# Uno_Shield.net
KiCad netlist of a schematic drawn in EAGLE
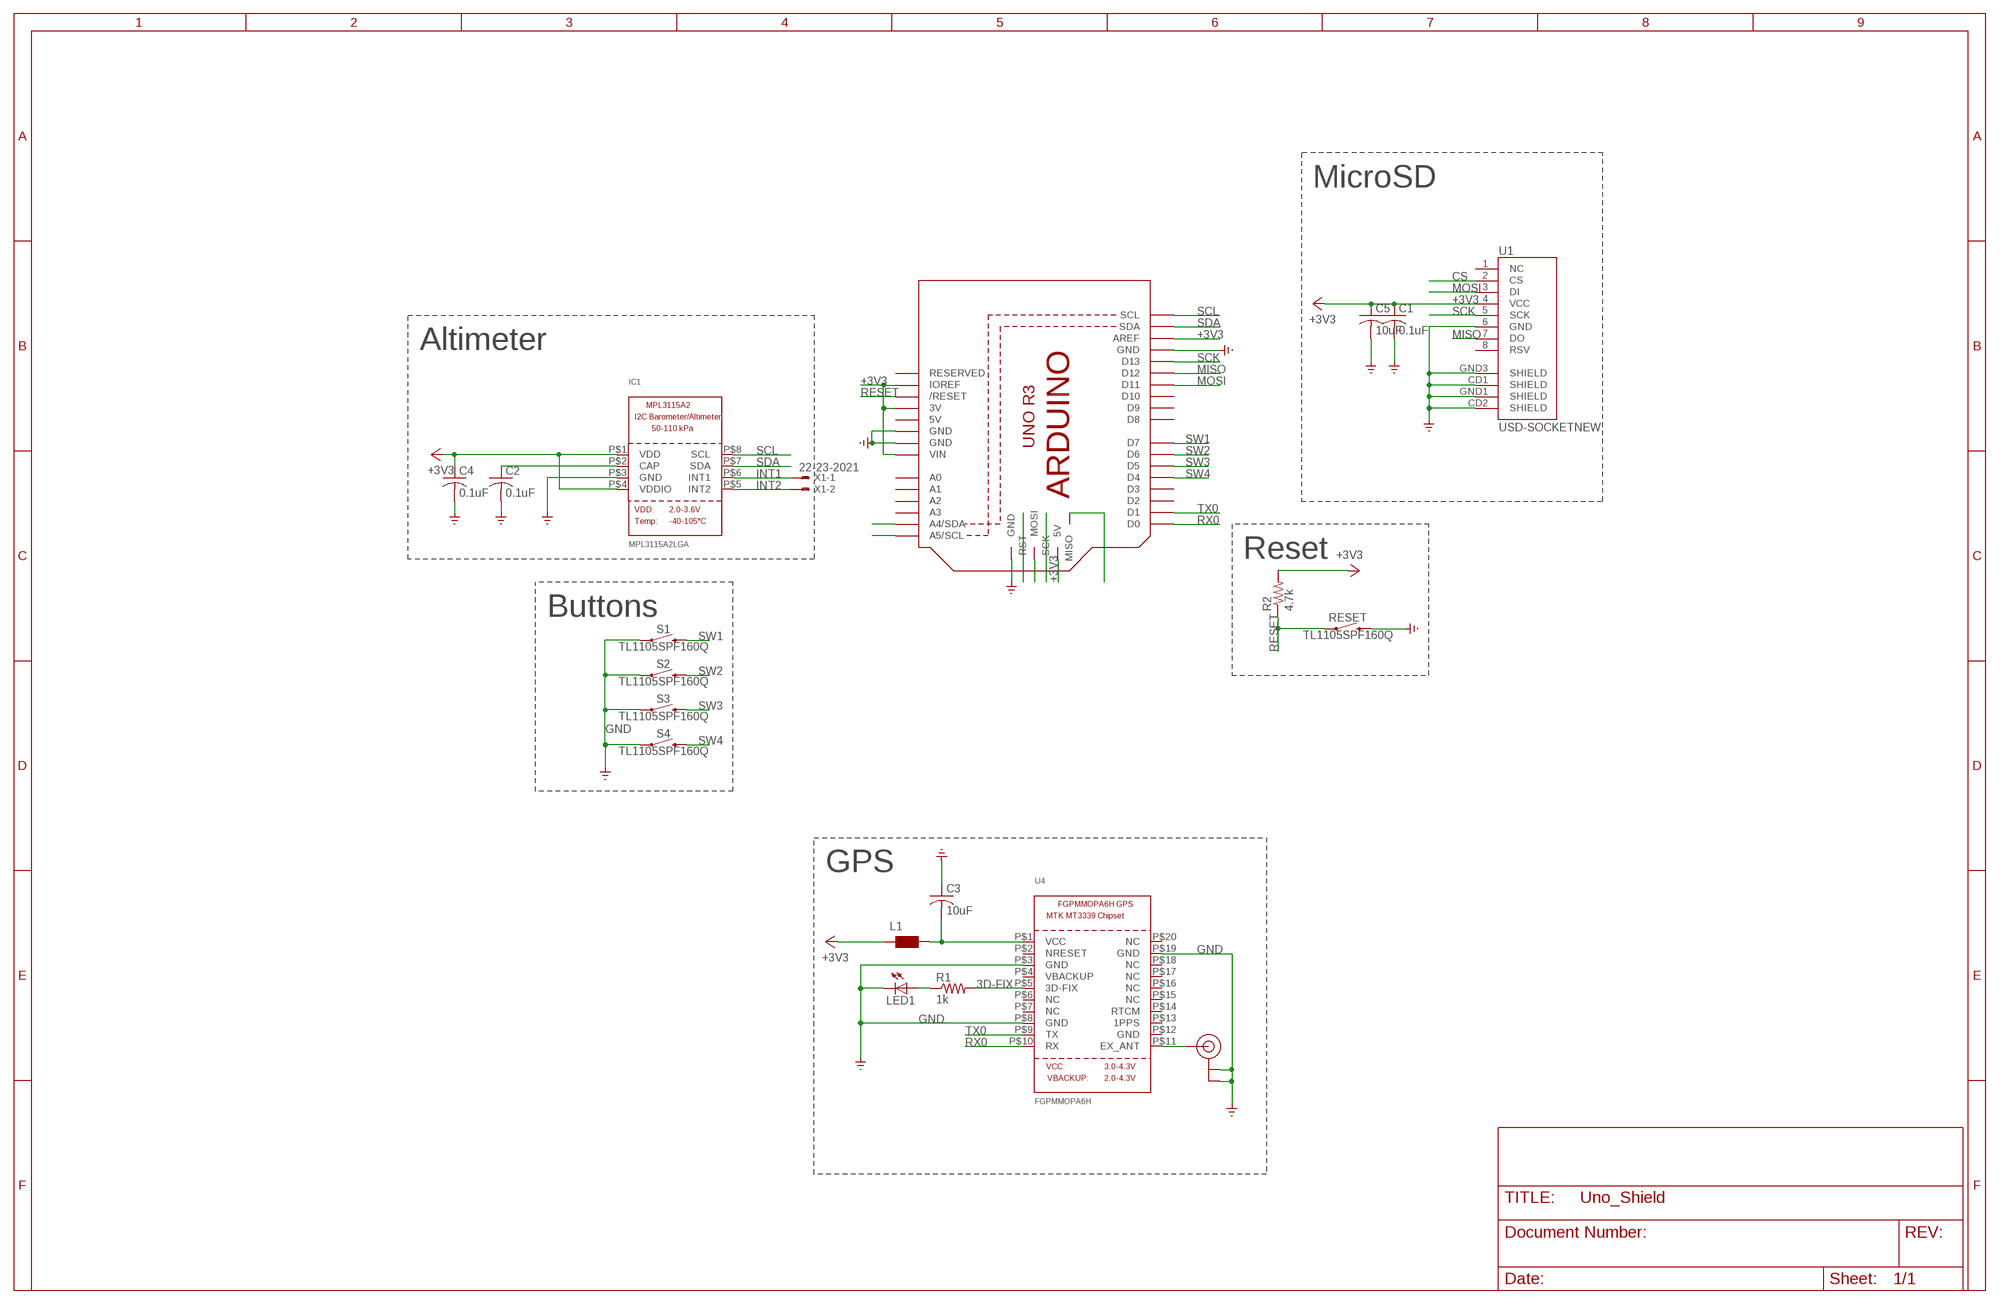
[diagram p0: schematic, sheet 1]

(export (version "E")
  (design (tool "Eeschema 10.0.6"))
  (components
    (comp (ref "C1")
      (value "0.1uF")
      (footprint "eagle-import:C1206")
      (libsource (lib "eagle-import") (part "C-USC1206"))
    )
    (comp (ref "C2")
      (value "0.1uF")
      (footprint "eagle-import:C1206")
      (libsource (lib "eagle-import") (part "C-USC1206"))
    )
    (comp (ref "C3")
      (value "10uF")
      (footprint "eagle-import:C1206")
      (libsource (lib "eagle-import") (part "C-USC1206"))
    )
    (comp (ref "C4")
      (value "0.1uF")
      (footprint "eagle-import:C1206")
      (libsource (lib "eagle-import") (part "C-USC1206"))
    )
    (comp (ref "C5")
      (value "10uF")
      (footprint "eagle-import:C1206")
      (libsource (lib "eagle-import") (part "C-USC1206"))
    )
    (comp (ref "IC1")
      (value "MPL3115A2LGA")
      (footprint "eagle-import:LGA8")
      (libsource (lib "eagle-import") (part "MPL3115A2LGA"))
    )
    (comp (ref "L1")
      (value "WE-CBF_1206")
      (footprint "eagle-import:1206")
      (libsource (lib "eagle-import") (part "WE-CBF_1206"))
    )
    (comp (ref "LED1")
      (value "LEDSMT1206")
      (footprint "eagle-import:1206")
      (libsource (lib "eagle-import") (part "LEDSMT1206"))
    )
    (comp (ref "M1")
      (value "ARDUINO_R3_ICSP")
      (footprint "eagle-import:ARDUINOR3_ICSP")
      (libsource (lib "eagle-import") (part "ARDUINO_R3_ICSP"))
    )
    (comp (ref "R1")
      (value "1k")
      (footprint "eagle-import:R1206")
      (libsource (lib "eagle-import") (part "R-US_R1206"))
    )
    (comp (ref "R2")
      (value "4.7k")
      (footprint "eagle-import:R1206")
      (libsource (lib "eagle-import") (part "R-US_R1206"))
    )
    (comp (ref "RESET")
      (value "TL1105SPF160Q")
      (footprint "eagle-import:TACTILE_SWITCH_PTH_6.0MM")
      (libsource (lib "eagle-import") (part "MOMENTARY-SWITCH-SPST-PTH-6.0MM"))
    )
    (comp (ref "S1")
      (value "TL1105SPF160Q")
      (footprint "eagle-import:TACTILE_SWITCH_PTH_6.0MM")
      (libsource (lib "eagle-import") (part "MOMENTARY-SWITCH-SPST-PTH-6.0MM"))
    )
    (comp (ref "S2")
      (value "TL1105SPF160Q")
      (footprint "eagle-import:TACTILE_SWITCH_PTH_6.0MM")
      (libsource (lib "eagle-import") (part "MOMENTARY-SWITCH-SPST-PTH-6.0MM"))
    )
    (comp (ref "S3")
      (value "TL1105SPF160Q")
      (footprint "eagle-import:TACTILE_SWITCH_PTH_6.0MM")
      (libsource (lib "eagle-import") (part "MOMENTARY-SWITCH-SPST-PTH-6.0MM"))
    )
    (comp (ref "S4")
      (value "TL1105SPF160Q")
      (footprint "eagle-import:TACTILE_SWITCH_PTH_6.0MM")
      (libsource (lib "eagle-import") (part "MOMENTARY-SWITCH-SPST-PTH-6.0MM"))
    )
    (comp (ref "U$20")
      (value "U.FL")
      (footprint "eagle-import:U.FL")
      (libsource (lib "eagle-import") (part "U.FL"))
    )
    (comp (ref "U1")
      (value "USD-SOCKETNEW")
      (footprint "eagle-import:MICRO-SD-SOCKET-PP")
      (libsource (lib "eagle-import") (part "USD-SOCKETNEW"))
    )
    (comp (ref "U4")
      (value "FGPMMOPA6H")
      (footprint "eagle-import:FGPMMOPA6H")
      (libsource (lib "eagle-import") (part "GPS_FGPMMOPA6H"))
    )
    (comp (ref "X1")
      (value "22-23-2021")
      (footprint "eagle-import:22-23-2021")
      (fields (field (name "MF") "MOLEX"))
      (libsource (lib "eagle-import") (part "22-23-2021"))
    )
  )
  (nets
    (net (code "1") (name "+3V3") (class "Default")
      (node (ref "C1") (pin "1") (pinfunction "1_1") (pintype "passive"))
      (node (ref "C4") (pin "1") (pinfunction "1_1") (pintype "passive"))
      (node (ref "C5") (pin "1") (pinfunction "1_1") (pintype "passive"))
      (node (ref "IC1") (pin "P$1") (pinfunction "VDD_P$1") (pintype "power_in"))
      (node (ref "IC1") (pin "P$4") (pinfunction "VDDIO_P$4") (pintype "power_in"))
      (node (ref "L1") (pin "1") (pinfunction "1_1") (pintype "passive"))
      (node (ref "M1") (pin "3V") (pinfunction "3V_3V") (pintype "power_in"))
      (node (ref "M1") (pin "5V_ICSP") (pinfunction "5V_5V_ICSP") (pintype "passive"))
      (node (ref "M1") (pin "AREF") (pinfunction "AREF_AREF") (pintype "bidirectional"))
      (node (ref "M1") (pin "IOREF") (pinfunction "IOREF_IOREF") (pintype "output"))
      (node (ref "M1") (pin "VIN") (pinfunction "VIN_VIN") (pintype "power_in"))
      (node (ref "R2") (pin "2") (pinfunction "2_2") (pintype "passive"))
      (node (ref "U1") (pin "4") (pinfunction "VCC_4") (pintype "bidirectional"))
    )
    (net (code "2") (name "/3D-FIX") (class "Default")
      (node (ref "R1") (pin "2") (pinfunction "2_2") (pintype "passive"))
      (node (ref "U4") (pin "P$5") (pinfunction "3D-FIX_P$5") (pintype "bidirectional"))
    )
    (net (code "3") (name "/5V") (class "Default")
      (node (ref "M1") (pin "5V") (pinfunction "5V_5V") (pintype "power_in"))
    )
    (net (code "4") (name "/CS") (class "Default")
      (node (ref "U1") (pin "2") (pinfunction "CS_2") (pintype "bidirectional"))
    )
    (net (code "5") (name "/INT1") (class "Default")
      (node (ref "IC1") (pin "P$6") (pinfunction "INT1_P$6") (pintype "output"))
      (node (ref "X1") (pin "1") (pinfunction "S_1") (pintype "passive"))
    )
    (net (code "6") (name "/INT2") (class "Default")
      (node (ref "IC1") (pin "P$5") (pinfunction "INT2_P$5") (pintype "output"))
      (node (ref "X1") (pin "2") (pinfunction "S_2") (pintype "passive"))
    )
    (net (code "7") (name "/MISO") (class "Default")
      (node (ref "M1") (pin "D12") (pinfunction "D12_D12") (pintype "bidirectional"))
      (node (ref "M1") (pin "MISO") (pinfunction "MISO_MISO") (pintype "passive"))
      (node (ref "U1") (pin "7") (pinfunction "DO_7") (pintype "bidirectional"))
    )
    (net (code "8") (name "/MOSI") (class "Default")
      (node (ref "M1") (pin "D11") (pinfunction "D11_D11") (pintype "bidirectional"))
      (node (ref "M1") (pin "MOSI") (pinfunction "MOSI_MOSI") (pintype "passive"))
      (node (ref "U1") (pin "3") (pinfunction "DI_3") (pintype "bidirectional"))
    )
    (net (code "9") (name "/RESET") (class "Default")
      (node (ref "M1") (pin "RESET") (pinfunction "/RESET_RESET") (pintype "bidirectional"))
      (node (ref "M1") (pin "RESET_ICSP") (pinfunction "RST_RESET_ICSP") (pintype "passive"))
      (node (ref "R2") (pin "1") (pinfunction "1_1") (pintype "passive"))
      (node (ref "RESET") (pin "1") (pinfunction "1_1") (pintype "passive"))
    )
    (net (code "10") (name "/RX0") (class "Default")
      (node (ref "M1") (pin "D0") (pinfunction "D0_D0") (pintype "bidirectional"))
      (node (ref "U4") (pin "P$10") (pinfunction "RX_P$10") (pintype "bidirectional"))
    )
    (net (code "11") (name "/SCK") (class "Default")
      (node (ref "M1") (pin "D13") (pinfunction "D13_D13") (pintype "bidirectional"))
      (node (ref "M1") (pin "SCK") (pinfunction "SCK_SCK") (pintype "passive"))
      (node (ref "U1") (pin "5") (pinfunction "SCK_5") (pintype "bidirectional"))
    )
    (net (code "12") (name "/SCL") (class "Default")
      (node (ref "IC1") (pin "P$8") (pinfunction "SCL_P$8") (pintype "bidirectional"))
      (node (ref "M1") (pin "A5") (pinfunction "A5/SCL_A5") (pintype "bidirectional"))
      (node (ref "M1") (pin "SCL") (pinfunction "SCL_SCL") (pintype "bidirectional"))
    )
    (net (code "13") (name "/SDA") (class "Default")
      (node (ref "IC1") (pin "P$7") (pinfunction "SDA_P$7") (pintype "bidirectional"))
      (node (ref "M1") (pin "A4") (pinfunction "A4/SDA_A4") (pintype "bidirectional"))
      (node (ref "M1") (pin "SDA") (pinfunction "SDA_SDA") (pintype "bidirectional"))
    )
    (net (code "14") (name "/SW1") (class "Default")
      (node (ref "M1") (pin "D7") (pinfunction "D7_D7") (pintype "bidirectional"))
      (node (ref "S1") (pin "3") (pinfunction "2_3") (pintype "passive"))
    )
    (net (code "15") (name "/SW2") (class "Default")
      (node (ref "M1") (pin "D6") (pinfunction "D6_D6") (pintype "bidirectional"))
      (node (ref "S2") (pin "3") (pinfunction "2_3") (pintype "passive"))
    )
    (net (code "16") (name "/SW3") (class "Default")
      (node (ref "M1") (pin "D5") (pinfunction "D5_D5") (pintype "bidirectional"))
      (node (ref "S3") (pin "3") (pinfunction "2_3") (pintype "passive"))
    )
    (net (code "17") (name "/SW4") (class "Default")
      (node (ref "M1") (pin "D4") (pinfunction "D4_D4") (pintype "bidirectional"))
      (node (ref "S4") (pin "3") (pinfunction "2_3") (pintype "passive"))
    )
    (net (code "18") (name "/TX0") (class "Default")
      (node (ref "M1") (pin "D1") (pinfunction "D1_D1") (pintype "bidirectional"))
      (node (ref "U4") (pin "P$9") (pinfunction "TX_P$9") (pintype "bidirectional"))
    )
    (net (code "19") (name "GND_") (class "Default")
      (node (ref "C1") (pin "2") (pinfunction "2_2") (pintype "passive"))
      (node (ref "C2") (pin "2") (pinfunction "2_2") (pintype "passive"))
      (node (ref "C3") (pin "1") (pinfunction "1_1") (pintype "passive"))
      (node (ref "C4") (pin "2") (pinfunction "2_2") (pintype "passive"))
      (node (ref "C5") (pin "2") (pinfunction "2_2") (pintype "passive"))
      (node (ref "IC1") (pin "P$3") (pinfunction "GND_P$3") (pintype "power_in"))
      (node (ref "LED1") (pin "C") (pinfunction "C_C") (pintype "passive"))
      (node (ref "M1") (pin "GND") (pinfunction "GND_GND") (pintype "power_in"))
      (node (ref "M1") (pin "GND@1") (pinfunction "GND_GND@1") (pintype "power_in"))
      (node (ref "M1") (pin "GND@2") (pinfunction "GND_GND@2") (pintype "passive"))
      (node (ref "M1") (pin "GND@3") (pinfunction "GND_GND@3") (pintype "power_in"))
      (node (ref "RESET") (pin "3") (pinfunction "2_3") (pintype "passive"))
      (node (ref "S1") (pin "1") (pinfunction "1_1") (pintype "passive"))
      (node (ref "S2") (pin "1") (pinfunction "1_1") (pintype "passive"))
      (node (ref "S3") (pin "1") (pinfunction "1_1") (pintype "passive"))
      (node (ref "S4") (pin "1") (pinfunction "1_1") (pintype "passive"))
      (node (ref "U$20") (pin "P$1") (pinfunction "GND_P$1") (pintype "bidirectional"))
      (node (ref "U$20") (pin "P$2") (pinfunction "GND_P$2") (pintype "bidirectional"))
      (node (ref "U1") (pin "6") (pinfunction "GND_6") (pintype "bidirectional"))
      (node (ref "U1") (pin "CD1") (pinfunction "SHIELD_CD1") (pintype "bidirectional"))
      (node (ref "U1") (pin "CD2") (pinfunction "SHIELD_CD2") (pintype "bidirectional"))
      (node (ref "U1") (pin "GND1") (pinfunction "SHIELD_GND1") (pintype "bidirectional"))
      (node (ref "U1") (pin "GND3") (pinfunction "SHIELD_GND3") (pintype "bidirectional"))
      (node (ref "U4") (pin "P$19") (pinfunction "GND_P$19") (pintype "bidirectional"))
      (node (ref "U4") (pin "P$3") (pinfunction "GND_P$3") (pintype "bidirectional"))
      (node (ref "U4") (pin "P$8") (pinfunction "GND_P$8") (pintype "bidirectional"))
    )
    (net (code "20") (name "Net-(IC1-CAP)") (class "Default")
      (node (ref "C2") (pin "1") (pinfunction "1_1") (pintype "passive"))
      (node (ref "IC1") (pin "P$2") (pinfunction "CAP_P$2") (pintype "passive"))
    )
    (net (code "21") (name "Net-(LED1-PadA)") (class "Default")
      (node (ref "LED1") (pin "A") (pinfunction "A_A") (pintype "passive"))
      (node (ref "R1") (pin "1") (pinfunction "1_1") (pintype "passive"))
    )
    (net (code "22") (name "Net-(U$20-SIGNAL)") (class "Default")
      (node (ref "U$20") (pin "P$3") (pinfunction "SIGNAL_P$3") (pintype "bidirectional"))
      (node (ref "U4") (pin "P$11") (pinfunction "EX_ANT_P$11") (pintype "bidirectional"))
    )
    (net (code "23") (name "Net-(U4-VCC)") (class "Default")
      (node (ref "C3") (pin "2") (pinfunction "2_2") (pintype "passive"))
      (node (ref "L1") (pin "2") (pinfunction "2_2") (pintype "passive"))
      (node (ref "U4") (pin "P$1") (pinfunction "VCC_P$1") (pintype "bidirectional"))
    )
    (net (code "24") (name "unconnected-(M1-PadA0)") (class "Default")
      (node (ref "M1") (pin "A0") (pinfunction "A0_A0") (pintype "bidirectional"))
    )
    (net (code "25") (name "unconnected-(M1-PadA1)") (class "Default")
      (node (ref "M1") (pin "A1") (pinfunction "A1_A1") (pintype "bidirectional"))
    )
    (net (code "26") (name "unconnected-(M1-PadA2)") (class "Default")
      (node (ref "M1") (pin "A2") (pinfunction "A2_A2") (pintype "bidirectional"))
    )
    (net (code "27") (name "unconnected-(M1-PadA3)") (class "Default")
      (node (ref "M1") (pin "A3") (pinfunction "A3_A3") (pintype "bidirectional"))
    )
    (net (code "28") (name "unconnected-(M1-PadD2)") (class "Default")
      (node (ref "M1") (pin "D2") (pinfunction "D2_D2") (pintype "bidirectional"))
    )
    (net (code "29") (name "unconnected-(M1-PadD3)") (class "Default")
      (node (ref "M1") (pin "D3") (pinfunction "D3_D3") (pintype "bidirectional"))
    )
    (net (code "30") (name "unconnected-(M1-PadD8)") (class "Default")
      (node (ref "M1") (pin "D8") (pinfunction "D8_D8") (pintype "bidirectional"))
    )
    (net (code "31") (name "unconnected-(M1-PadD9)") (class "Default")
      (node (ref "M1") (pin "D9") (pinfunction "D9_D9") (pintype "bidirectional"))
    )
    (net (code "32") (name "unconnected-(M1-PadD10)") (class "Default")
      (node (ref "M1") (pin "D10") (pinfunction "D10_D10") (pintype "bidirectional"))
    )
    (net (code "33") (name "unconnected-(M1-PadRESERVED)") (class "Default")
      (node (ref "M1") (pin "RESERVED") (pinfunction "RESERVED_RESERVED") (pintype "no_connect"))
    )
    (net (code "34") (name "unconnected-(U1-NC-Pad1)") (class "Default")
      (node (ref "U1") (pin "1") (pinfunction "NC_1") (pintype "bidirectional"))
    )
    (net (code "35") (name "unconnected-(U1-RSV-Pad8)") (class "Default")
      (node (ref "U1") (pin "8") (pinfunction "RSV_8") (pintype "bidirectional"))
    )
    (net (code "36") (name "unconnected-(U4-1PPS-PadP$13)") (class "Default")
      (node (ref "U4") (pin "P$13") (pinfunction "1PPS_P$13") (pintype "bidirectional"))
    )
    (net (code "37") (name "unconnected-(U4-GND-PadP$12)") (class "Default")
      (node (ref "U4") (pin "P$12") (pinfunction "GND_P$12") (pintype "bidirectional"))
    )
    (net (code "38") (name "unconnected-(U4-NC-PadP$6)") (class "Default")
      (node (ref "U4") (pin "P$6") (pinfunction "NC_P$6") (pintype "bidirectional"))
    )
    (net (code "39") (name "unconnected-(U4-NC-PadP$7)") (class "Default")
      (node (ref "U4") (pin "P$7") (pinfunction "NC_P$7") (pintype "bidirectional"))
    )
    (net (code "40") (name "unconnected-(U4-NC-PadP$15)") (class "Default")
      (node (ref "U4") (pin "P$15") (pinfunction "NC_P$15") (pintype "bidirectional"))
    )
    (net (code "41") (name "unconnected-(U4-NC-PadP$16)") (class "Default")
      (node (ref "U4") (pin "P$16") (pinfunction "NC_P$16") (pintype "bidirectional"))
    )
    (net (code "42") (name "unconnected-(U4-NC-PadP$17)") (class "Default")
      (node (ref "U4") (pin "P$17") (pinfunction "NC_P$17") (pintype "bidirectional"))
    )
    (net (code "43") (name "unconnected-(U4-NC-PadP$18)") (class "Default")
      (node (ref "U4") (pin "P$18") (pinfunction "NC_P$18") (pintype "bidirectional"))
    )
    (net (code "44") (name "unconnected-(U4-NC-PadP$20)") (class "Default")
      (node (ref "U4") (pin "P$20") (pinfunction "NC_P$20") (pintype "bidirectional"))
    )
    (net (code "45") (name "unconnected-(U4-NRESET-PadP$2)") (class "Default")
      (node (ref "U4") (pin "P$2") (pinfunction "NRESET_P$2") (pintype "bidirectional"))
    )
    (net (code "46") (name "unconnected-(U4-RTCM-PadP$14)") (class "Default")
      (node (ref "U4") (pin "P$14") (pinfunction "RTCM_P$14") (pintype "bidirectional"))
    )
    (net (code "47") (name "unconnected-(U4-VBACKUP-PadP$4)") (class "Default")
      (node (ref "U4") (pin "P$4") (pinfunction "VBACKUP_P$4") (pintype "bidirectional"))
    )
  )
)
